# PIC18F26J50.net
KiCad netlist of a schematic drawn in EAGLE
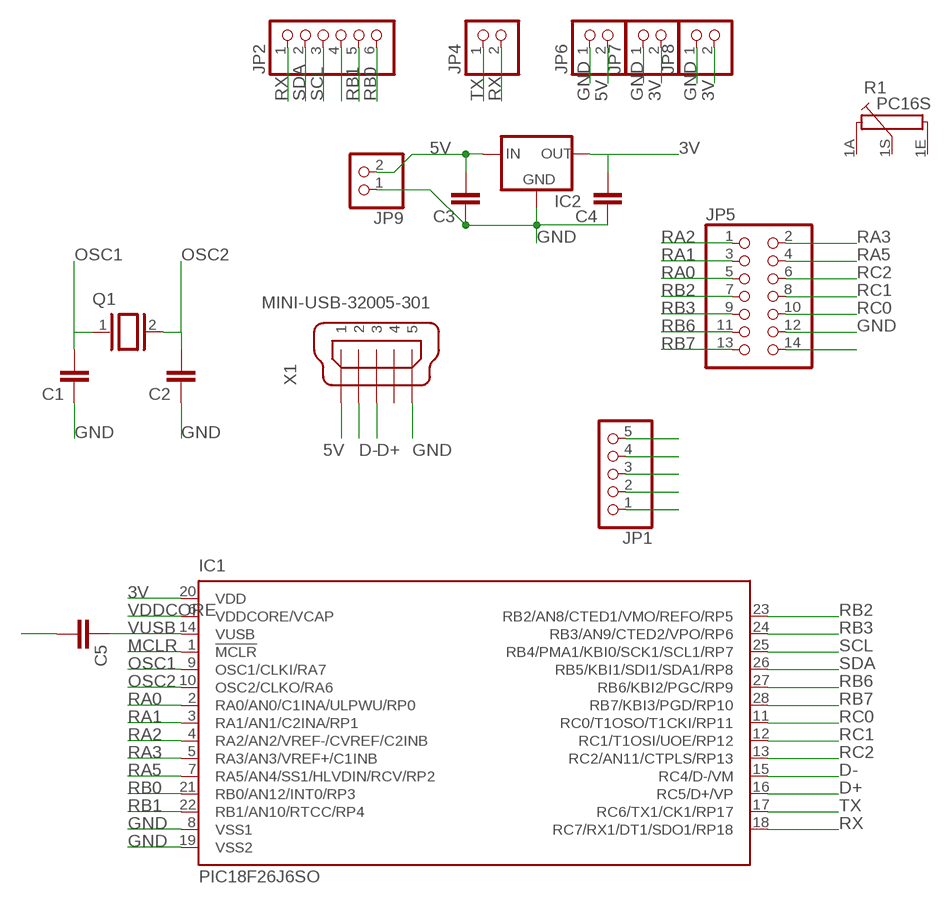
[diagram p0: schematic, sheet 1]

(export (version "E")
  (design (tool "Eeschema 10.0.6"))
  (components
    (comp (ref "C1")
      (value "C-EU025-025X050")
      (footprint "eagle-import:C025-025X050")
      (libsource (lib "eagle-import") (part "C-EU025-025X050"))
    )
    (comp (ref "C2")
      (value "C-EU025-025X050")
      (footprint "eagle-import:C025-025X050")
      (libsource (lib "eagle-import") (part "C-EU025-025X050"))
    )
    (comp (ref "C3")
      (value "C-EU025-025X050")
      (footprint "eagle-import:C025-025X050")
      (libsource (lib "eagle-import") (part "C-EU025-025X050"))
    )
    (comp (ref "C4")
      (value "C-EU025-025X050")
      (footprint "eagle-import:C025-025X050")
      (libsource (lib "eagle-import") (part "C-EU025-025X050"))
    )
    (comp (ref "C5")
      (value "C-EU025-025X050")
      (footprint "eagle-import:C025-025X050")
      (libsource (lib "eagle-import") (part "C-EU025-025X050"))
    )
    (comp (ref "IC1")
      (value "PIC18F26J6SO")
      (footprint "eagle-import:SO28W")
      (fields (field (name "MPN") "PIC18F26J53-I/SO"))
      (libsource (lib "eagle-import") (part "PIC18F26JSO6"))
    )
    (comp (ref "IC2")
      (value "78LXX-SOT89")
      (footprint "eagle-import:SOT89")
      (libsource (lib "eagle-import") (part "78LXX-SOT89"))
    )
    (comp (ref "JP1")
      (value "PINHD-1X5")
      (footprint "eagle-import:1X05")
      (libsource (lib "eagle-import") (part "PINHD-1X5"))
    )
    (comp (ref "JP2")
      (value "PINHD-1X6")
      (footprint "eagle-import:1X06")
      (libsource (lib "eagle-import") (part "PINHD-1X6"))
    )
    (comp (ref "JP4")
      (value "PINHD-1X2")
      (footprint "eagle-import:1X02")
      (libsource (lib "eagle-import") (part "PINHD-1X2"))
    )
    (comp (ref "JP5")
      (value "PINHD-2X7")
      (footprint "eagle-import:2X07")
      (libsource (lib "eagle-import") (part "PINHD-2X7"))
    )
    (comp (ref "JP6")
      (value "PINHD-1X2")
      (footprint "eagle-import:1X02")
      (libsource (lib "eagle-import") (part "PINHD-1X2"))
    )
    (comp (ref "JP7")
      (value "PINHD-1X2")
      (footprint "eagle-import:1X02")
      (libsource (lib "eagle-import") (part "PINHD-1X2"))
    )
    (comp (ref "JP8")
      (value "PINHD-1X2")
      (footprint "eagle-import:1X02")
      (libsource (lib "eagle-import") (part "PINHD-1X2"))
    )
    (comp (ref "JP9")
      (value "PINHD-1X2")
      (footprint "eagle-import:1X02")
      (libsource (lib "eagle-import") (part "PINHD-1X2"))
    )
    (comp (ref "Q1")
      (value "XTAL/S")
      (footprint "eagle-import:QS")
      (libsource (lib "eagle-import") (part "XTAL/S"))
    )
    (comp (ref "R1")
      (value "PC16S")
      (footprint "eagle-import:PC16S")
      (libsource (lib "eagle-import") (part "PC16S"))
    )
    (comp (ref "X1")
      (value "MINI-USB-32005-301")
      (footprint "eagle-import:32005-301")
      (libsource (lib "eagle-import") (part "MINI-USB-32005-301"))
    )
  )
  (nets
    (net (code "1") (name "/3V") (class "Default")
      (node (ref "C4") (pin "2") (pinfunction "2_2") (pintype "passive"))
      (node (ref "IC1") (pin "20") (pinfunction "VDD_20") (pintype "input"))
      (node (ref "IC2") (pin "1") (pinfunction "OUT_1") (pintype "passive"))
      (node (ref "JP1") (pin "4") (pinfunction "4_4") (pintype "passive"))
      (node (ref "JP7") (pin "2") (pinfunction "2_2") (pintype "passive"))
      (node (ref "JP8") (pin "2") (pinfunction "2_2") (pintype "passive"))
    )
    (net (code "2") (name "/5V") (class "Default")
      (node (ref "C3") (pin "2") (pinfunction "2_2") (pintype "passive"))
      (node (ref "IC2") (pin "3") (pinfunction "IN_3") (pintype "input"))
      (node (ref "JP6") (pin "2") (pinfunction "2_2") (pintype "passive"))
      (node (ref "JP9") (pin "2") (pinfunction "2_2") (pintype "passive"))
      (node (ref "X1") (pin "1") (pinfunction "1_1") (pintype "passive"))
    )
    (net (code "3") (name "/D+") (class "Default")
      (node (ref "IC1") (pin "16") (pinfunction "RC5/D+/VP_16") (pintype "bidirectional"))
      (node (ref "X1") (pin "3") (pinfunction "3_3") (pintype "passive"))
    )
    (net (code "4") (name "/D-") (class "Default")
      (node (ref "IC1") (pin "15") (pinfunction "RC4/D-/VM_15") (pintype "bidirectional"))
      (node (ref "X1") (pin "2") (pinfunction "2_2") (pintype "passive"))
    )
    (net (code "5") (name "/GND") (class "Default")
      (node (ref "C1") (pin "1") (pinfunction "1_1") (pintype "passive"))
      (node (ref "C2") (pin "1") (pinfunction "1_1") (pintype "passive"))
      (node (ref "C3") (pin "1") (pinfunction "1_1") (pintype "passive"))
      (node (ref "C4") (pin "1") (pinfunction "1_1") (pintype "passive"))
      (node (ref "C5") (pin "2") (pinfunction "2_2") (pintype "passive"))
      (node (ref "IC1") (pin "19") (pinfunction "VSS2_19") (pintype "input"))
      (node (ref "IC1") (pin "8") (pinfunction "VSS1_8") (pintype "input"))
      (node (ref "IC2") (pin "2") (pinfunction "GND_2") (pintype "input"))
      (node (ref "JP1") (pin "5") (pinfunction "5_5") (pintype "passive"))
      (node (ref "JP5") (pin "12") (pinfunction "12_12") (pintype "passive"))
      (node (ref "JP5") (pin "14") (pinfunction "14_14") (pintype "passive"))
      (node (ref "JP6") (pin "1") (pinfunction "1_1") (pintype "passive"))
      (node (ref "JP7") (pin "1") (pinfunction "1_1") (pintype "passive"))
      (node (ref "JP8") (pin "1") (pinfunction "1_1") (pintype "passive"))
      (node (ref "JP9") (pin "1") (pinfunction "1_1") (pintype "passive"))
      (node (ref "X1") (pin "5") (pinfunction "5_5") (pintype "passive"))
    )
    (net (code "6") (name "/MCLR") (class "Default")
      (node (ref "IC1") (pin "1") (pinfunction "~{MCLR}_1") (pintype "input"))
      (node (ref "JP1") (pin "1") (pinfunction "1_1") (pintype "passive"))
    )
    (net (code "7") (name "/OSC1") (class "Default")
      (node (ref "C1") (pin "2") (pinfunction "2_2") (pintype "passive"))
      (node (ref "IC1") (pin "9") (pinfunction "OSC1/CLKI/RA7_9") (pintype "bidirectional"))
      (node (ref "Q1") (pin "1") (pinfunction "1_1") (pintype "passive"))
    )
    (net (code "8") (name "/OSC2") (class "Default")
      (node (ref "C2") (pin "2") (pinfunction "2_2") (pintype "passive"))
      (node (ref "IC1") (pin "10") (pinfunction "OSC2/CLKO/RA6_10") (pintype "bidirectional"))
      (node (ref "Q1") (pin "2") (pinfunction "2_2") (pintype "passive"))
    )
    (net (code "9") (name "/RA0") (class "Default")
      (node (ref "IC1") (pin "2") (pinfunction "RA0/AN0/C1INA/ULPWU/RP0_2") (pintype "bidirectional"))
      (node (ref "JP5") (pin "5") (pinfunction "5_5") (pintype "passive"))
    )
    (net (code "10") (name "/RA1") (class "Default")
      (node (ref "IC1") (pin "3") (pinfunction "RA1/AN1/C2INA/RP1_3") (pintype "bidirectional"))
      (node (ref "JP5") (pin "3") (pinfunction "3_3") (pintype "passive"))
    )
    (net (code "11") (name "/RA2") (class "Default")
      (node (ref "IC1") (pin "4") (pinfunction "RA2/AN2/VREF-/CVREF/C2INB_4") (pintype "bidirectional"))
      (node (ref "JP5") (pin "1") (pinfunction "1_1") (pintype "passive"))
    )
    (net (code "12") (name "/RA3") (class "Default")
      (node (ref "IC1") (pin "5") (pinfunction "RA3/AN3/VREF+/C1INB_5") (pintype "bidirectional"))
      (node (ref "JP5") (pin "2") (pinfunction "2_2") (pintype "passive"))
    )
    (net (code "13") (name "/RA5") (class "Default")
      (node (ref "IC1") (pin "7") (pinfunction "RA5/AN4/SS1/HLVDIN/RCV/RP2_7") (pintype "bidirectional"))
      (node (ref "JP5") (pin "4") (pinfunction "4_4") (pintype "passive"))
    )
    (net (code "14") (name "/RB0") (class "Default")
      (node (ref "IC1") (pin "21") (pinfunction "RB0/AN12/INT0/RP3_21") (pintype "bidirectional"))
      (node (ref "JP2") (pin "6") (pinfunction "6_6") (pintype "passive"))
    )
    (net (code "15") (name "/RB1") (class "Default")
      (node (ref "IC1") (pin "22") (pinfunction "RB1/AN10/RTCC/RP4_22") (pintype "bidirectional"))
      (node (ref "JP2") (pin "5") (pinfunction "5_5") (pintype "passive"))
    )
    (net (code "16") (name "/RB2") (class "Default")
      (node (ref "IC1") (pin "23") (pinfunction "RB2/AN8/CTED1/VMO/REFO/RP5_23") (pintype "bidirectional"))
      (node (ref "JP2") (pin "4") (pinfunction "4_4") (pintype "passive"))
      (node (ref "JP5") (pin "7") (pinfunction "7_7") (pintype "passive"))
    )
    (net (code "17") (name "/RB3") (class "Default")
      (node (ref "IC1") (pin "24") (pinfunction "RB3/AN9/CTED2/VPO/RP6_24") (pintype "bidirectional"))
      (node (ref "JP5") (pin "9") (pinfunction "9_9") (pintype "passive"))
    )
    (net (code "18") (name "/RB6") (class "Default")
      (node (ref "IC1") (pin "27") (pinfunction "RB6/KBI2/PGC/RP9_27") (pintype "bidirectional"))
      (node (ref "JP1") (pin "2") (pinfunction "2_2") (pintype "passive"))
      (node (ref "JP5") (pin "11") (pinfunction "11_11") (pintype "passive"))
    )
    (net (code "19") (name "/RB7") (class "Default")
      (node (ref "IC1") (pin "28") (pinfunction "RB7/KBI3/PGD/RP10_28") (pintype "bidirectional"))
      (node (ref "JP1") (pin "3") (pinfunction "3_3") (pintype "passive"))
      (node (ref "JP5") (pin "13") (pinfunction "13_13") (pintype "passive"))
    )
    (net (code "20") (name "/RC0") (class "Default")
      (node (ref "IC1") (pin "11") (pinfunction "RC0/T1OSO/T1CKI/RP11_11") (pintype "bidirectional"))
      (node (ref "JP5") (pin "10") (pinfunction "10_10") (pintype "passive"))
    )
    (net (code "21") (name "/RC1") (class "Default")
      (node (ref "IC1") (pin "12") (pinfunction "RC1/T1OSI/UOE/RP12_12") (pintype "bidirectional"))
      (node (ref "JP5") (pin "8") (pinfunction "8_8") (pintype "passive"))
    )
    (net (code "22") (name "/RC2") (class "Default")
      (node (ref "IC1") (pin "13") (pinfunction "RC2/AN11/CTPLS/RP13_13") (pintype "bidirectional"))
      (node (ref "JP5") (pin "6") (pinfunction "6_6") (pintype "passive"))
    )
    (net (code "23") (name "/RX") (class "Default")
      (node (ref "IC1") (pin "18") (pinfunction "RC7/RX1/DT1/SDO1/RP18_18") (pintype "bidirectional"))
      (node (ref "JP2") (pin "1") (pinfunction "1_1") (pintype "passive"))
      (node (ref "JP4") (pin "2") (pinfunction "2_2") (pintype "passive"))
    )
    (net (code "24") (name "/SCL") (class "Default")
      (node (ref "IC1") (pin "25") (pinfunction "RB4/PMA1/KBI0/SCK1/SCL1/RP7_25") (pintype "bidirectional"))
      (node (ref "JP2") (pin "3") (pinfunction "3_3") (pintype "passive"))
    )
    (net (code "25") (name "/SDA") (class "Default")
      (node (ref "IC1") (pin "26") (pinfunction "RB5/KBI1/SDI1/SDA1/RP8_26") (pintype "bidirectional"))
      (node (ref "JP2") (pin "2") (pinfunction "2_2") (pintype "passive"))
    )
    (net (code "26") (name "/TX") (class "Default")
      (node (ref "IC1") (pin "17") (pinfunction "RC6/TX1/CK1/RP17_17") (pintype "bidirectional"))
      (node (ref "JP4") (pin "1") (pinfunction "1_1") (pintype "passive"))
    )
    (net (code "27") (name "/VDDCORE") (class "Default")
      (node (ref "IC1") (pin "6") (pinfunction "VDDCORE/VCAP_6") (pintype "input"))
    )
    (net (code "28") (name "/VUSB") (class "Default")
      (node (ref "C5") (pin "1") (pinfunction "1_1") (pintype "passive"))
      (node (ref "IC1") (pin "14") (pinfunction "VUSB_14") (pintype "input"))
    )
    (net (code "29") (name "unconnected-(R1-Pad1A)") (class "Default")
      (node (ref "R1") (pin "1A") (pinfunction "1A_1A") (pintype "passive"))
    )
    (net (code "30") (name "unconnected-(R1-Pad1E)") (class "Default")
      (node (ref "R1") (pin "1E") (pinfunction "1E_1E") (pintype "passive"))
    )
    (net (code "31") (name "unconnected-(R1-Pad1S)") (class "Default")
      (node (ref "R1") (pin "1S") (pinfunction "1S_1S") (pintype "passive"))
    )
    (net (code "32") (name "unconnected-(X1-Pad4)") (class "Default")
      (node (ref "X1") (pin "4") (pinfunction "4_4") (pintype "passive"))
    )
  )
)
